# Power_Supply_Noise_Canceller.net
KiCad netlist of a schematic drawn in Altium Designer
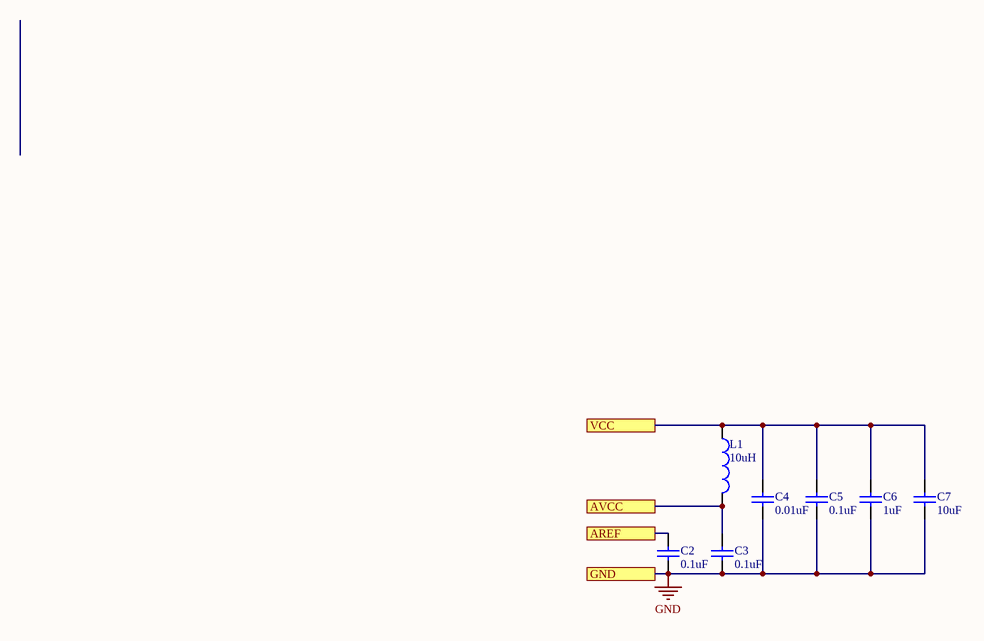
[diagram p0: Power Supply Noise Canceller.SchDoc]

(export (version "E")
  (design (tool "Eeschema 10.0.6"))
  (components
    (comp (ref "C2")
      (value "0.1uF")
      (footprint "CAPC2013X94X50LL20T25")
      (description "Chip Capacitor, 0.1 uF, +/- 5%, 50 V, -55 to 125 degC, 0805 (2012 Metric), RoHS, Tape and Reel")
      (fields (field (name "TOLERANCE") "5%") (field (name "MANUFACTURER") "AVX"))
      (libsource (lib "Altium Content Vault") (part "CAP-NP-2"))
    )
    (comp (ref "C3")
      (value "0.1uF")
      (footprint "CAPC2013X94X50LL20T25")
      (description "Chip Capacitor, 0.1 uF, +/- 5%, 50 V, -55 to 125 degC, 0805 (2012 Metric), RoHS, Tape and Reel")
      (fields (field (name "TOLERANCE") "5%") (field (name "MANUFACTURER") "AVX"))
      (libsource (lib "Altium Content Vault") (part "CAP-NP-2"))
    )
    (comp (ref "C4")
      (value "0.01uF")
      (footprint "CAPC2013X88X50LL20T25")
      (description "Chip Capacitor, 0.01 uF, +/- 10%, 50 V, -55 to 125 degC, 0805 (2012 Metric), RoHS, Tape and Reel")
      (fields (field (name "MANUFACTURER") "Kemet") (field (name "TOLERANCE") "10%"))
      (libsource (lib "Altium Content Vault") (part "CAP-NP-2"))
    )
    (comp (ref "C5")
      (value "0.1uF")
      (footprint "CAPC2013X94X50LL20T25")
      (description "Chip Capacitor, 0.1 uF, +/- 5%, 50 V, -55 to 125 degC, 0805 (2012 Metric), RoHS, Tape and Reel")
      (fields (field (name "TOLERANCE") "5%") (field (name "MANUFACTURER") "AVX"))
      (libsource (lib "Altium Content Vault") (part "CAP-NP-2"))
    )
    (comp (ref "C6")
      (value "1uF")
      (footprint "CAPC2013X145X50ML20T25")
      (description "Chip Capacitor, 1 uF, 25 V, 10%, -55 to 125 degC, 0805 (2012 Metric), RoHS, Tape and Reel")
      (fields (field (name "MANUFACTURER") "Yageo") (field (name "TOLERANCE") "10%"))
      (libsource (lib "Altium Content Vault") (part "CAP-NP-2"))
    )
    (comp (ref "C7")
      (value "10uF")
      (footprint "CAPC2013X145X50LL20T20")
      (description "Chip Capacitor, 10 uF, +/- 10%, 10 V, -55 to 85 degC, 0805 (2012 Metric), RoHS, Tape and Reel")
      (fields (field (name "MANUFACTURER") "Vishay") (field (name "TOLERANCE") "10%"))
      (libsource (lib "Altium Content Vault") (part "CAP-NP-2"))
    )
    (comp (ref "L1")
      (value "10uH")
      (footprint "TDK-IND0805-125_V")
      (description "Multilayer Inductor, 10 uH, ±20%, 300 mOhm, 50MHz, 0805(2012)")
      (fields (field (name "PARTNUMBER") "MLZ2012N100LT"))
      (libsource (lib "Altium Content Vault") (part "TDK-IND_INDUCTOR-2"))
    )
  )
  (nets
    (net (code "1") (name "/AREF") (class "Default")
      (node (ref "C2") (pin "2") (pinfunction "2_2") (pintype "passive"))
    )
    (net (code "2") (name "/AVCC") (class "Default")
      (node (ref "C3") (pin "2") (pinfunction "2_2") (pintype "passive"))
      (node (ref "L1") (pin "2") (pinfunction "2_2") (pintype "passive"))
    )
    (net (code "3") (name "/VCC") (class "Default")
      (node (ref "C4") (pin "2") (pinfunction "2_2") (pintype "passive"))
      (node (ref "C5") (pin "2") (pinfunction "2_2") (pintype "passive"))
      (node (ref "C6") (pin "2") (pinfunction "2_2") (pintype "passive"))
      (node (ref "C7") (pin "2") (pinfunction "2_2") (pintype "passive"))
      (node (ref "L1") (pin "1") (pinfunction "1_1") (pintype "passive"))
    )
    (net (code "4") (name "GND") (class "Default")
      (node (ref "C2") (pin "1") (pinfunction "1_1") (pintype "passive"))
      (node (ref "C3") (pin "1") (pinfunction "1_1") (pintype "passive"))
      (node (ref "C4") (pin "1") (pinfunction "1_1") (pintype "passive"))
      (node (ref "C5") (pin "1") (pinfunction "1_1") (pintype "passive"))
      (node (ref "C6") (pin "1") (pinfunction "1_1") (pintype "passive"))
      (node (ref "C7") (pin "1") (pinfunction "1_1") (pintype "passive"))
    )
  )
)
